# Sheet_1_2021-04-14.net
KiCad netlist of a schematic drawn in Altium Designer
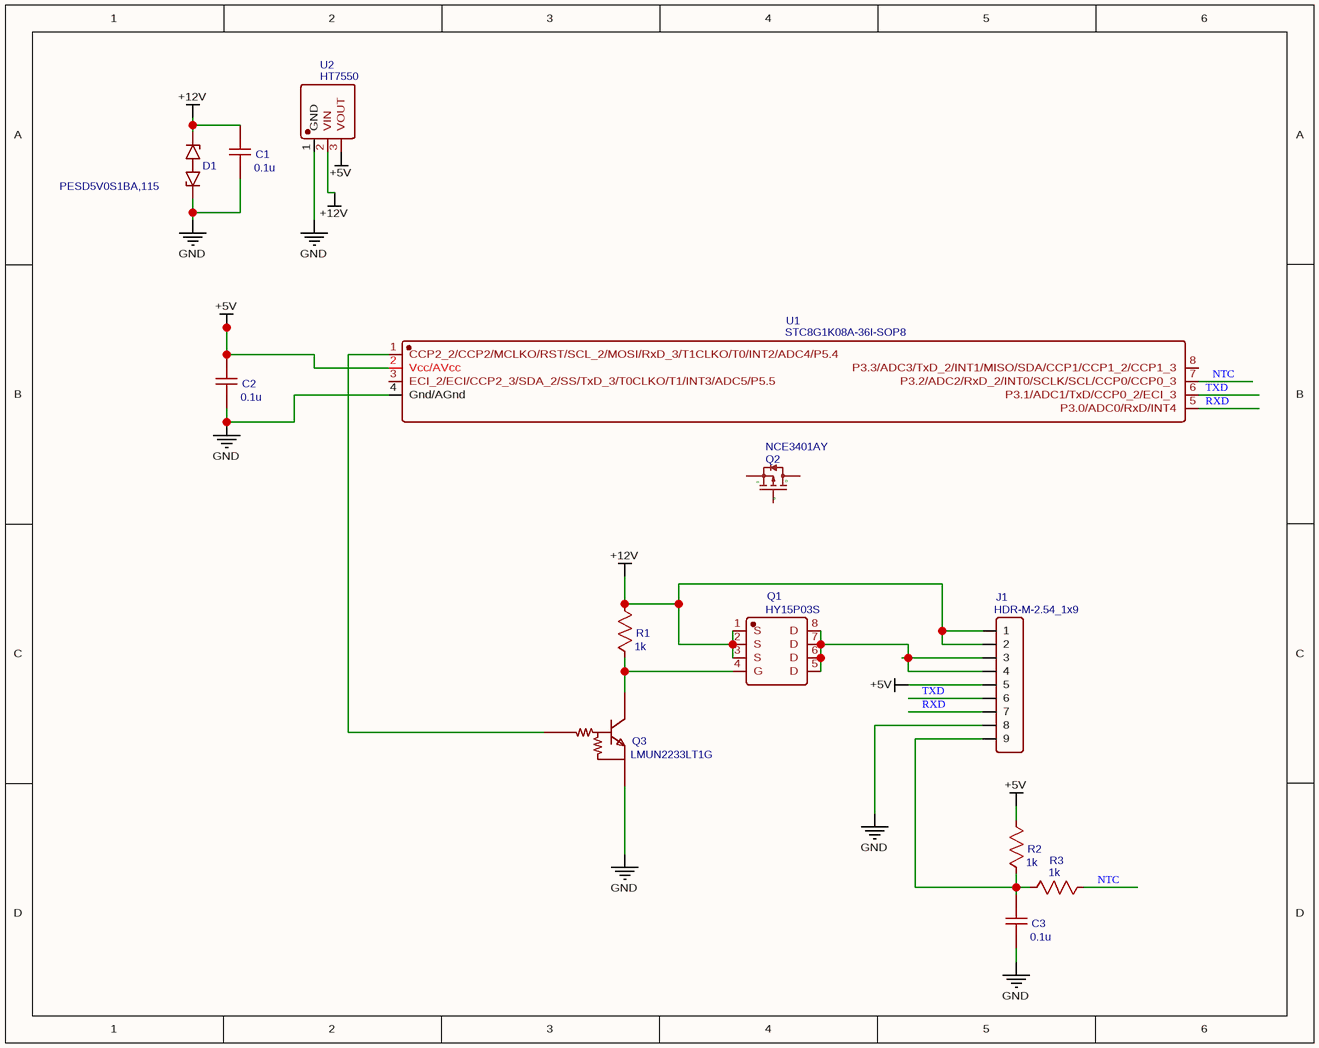
[diagram p0: Sheet_1_2021-04-14.schdoc]

(export (version "E")
  (design (tool "Eeschema 10.0.6"))
  (components
    (comp (ref "C1")
      (value "0.1u")
      (fields (field (name "CONTRIBUTOR") "LCEDA_Lib"))
      (libsource (lib "altium-import") (part "root_1_0.1u_"))
    )
    (comp (ref "C2")
      (value "0.1u")
      (fields (field (name "CONTRIBUTOR") "LCEDA_Lib"))
      (libsource (lib "altium-import") (part "root_1_0.1u_"))
    )
    (comp (ref "C3")
      (value "0.1u")
      (fields (field (name "CONTRIBUTOR") "LCEDA_Lib"))
      (libsource (lib "altium-import") (part "root_1_0.1u_"))
    )
    (comp (ref "D1")
      (value "PESD5V0S1BA,115")
      (fields (field (name "BOM_SUPPLIER PART") "C19224"))
      (libsource (lib "altium-import") (part "root_1_PESD5V0S1BA,115_"))
    )
    (comp (ref "J1")
      (value "HDR-M-2.54_1x9")
      (fields (field (name "BOM_SUPPLIER PART") "C225484") (field (name "CONTRIBUTOR") "LCEDA_Lib"))
      (libsource (lib "altium-import") (part "root_0_HDR-M-2.54_1x9_"))
    )
    (comp (ref "Q1")
      (value "HY15P03S")
      (fields (field (name "BOM_SUPPLIER PART") "C122494"))
      (libsource (lib "altium-import") (part "root_0_HY15P03S_"))
    )
    (comp (ref "Q2")
      (value "NCE3401AY")
      (fields (field (name "BOM_SUPPLIER PART") "C169815") (field (name "CONTRIBUTOR") "LCSC"))
      (libsource (lib "altium-import") (part "root_3_NCE3401AY_"))
    )
    (comp (ref "Q3")
      (value "LMUN2233LT1G")
      (fields (field (name "BOM_SUPPLIER PART") "C12777"))
      (libsource (lib "altium-import") (part "root_0_LMUN2233LT1G_"))
    )
    (comp (ref "R1")
      (value "1k")
      (fields (field (name "CONTRIBUTOR") "LCEDA_Lib"))
      (libsource (lib "altium-import") (part "root_1_1k_"))
    )
    (comp (ref "R2")
      (value "1k")
      (fields (field (name "CONTRIBUTOR") "LCEDA_Lib"))
      (libsource (lib "altium-import") (part "root_1_1k_"))
    )
    (comp (ref "R3")
      (value "1k")
      (fields (field (name "CONTRIBUTOR") "LCEDA_Lib"))
      (libsource (lib "altium-import") (part "root_2_1k_"))
    )
    (comp (ref "U1")
      (value "STC8G1K08A-36I-SOP8")
      (fields (field (name "BOM_SUPPLIER PART") "C915663") (field (name "CONTRIBUTOR") "LCSC"))
      (libsource (lib "altium-import") (part "root_0_STC8G1K08A-36I-SOP8_"))
    )
    (comp (ref "U2")
      (value "HT7550")
      (fields (field (name "BOM_SUPPLIER PART") "C499635") (field (name "CONTRIBUTOR") "LCSC"))
      (libsource (lib "altium-import") (part "root_1_HT7550_"))
    )
  )
  (nets
    (net (code "1") (name "+5V") (class "Default")
      (node (ref "C2") (pin "2") (pinfunction "2_2") (pintype "passive"))
      (node (ref "J1") (pin "5") (pinfunction "5_5") (pintype "passive"))
      (node (ref "R2") (pin "2") (pinfunction "2_2") (pintype "passive"))
      (node (ref "U1") (pin "2") (pinfunction "Vcc/AVcc_2") (pintype "passive"))
      (node (ref "U2") (pin "3") (pinfunction "VOUT_3") (pintype "passive"))
    )
    (net (code "2") (name "+12V") (class "Default")
      (node (ref "C1") (pin "2") (pinfunction "2_2") (pintype "passive"))
      (node (ref "D1") (pin "2") (pinfunction "2_2") (pintype "passive"))
      (node (ref "J1") (pin "1") (pinfunction "1_1") (pintype "passive"))
      (node (ref "J1") (pin "2") (pinfunction "2_2") (pintype "passive"))
      (node (ref "Q1") (pin "1") (pinfunction "S_1") (pintype "passive"))
      (node (ref "Q1") (pin "2") (pinfunction "S_2") (pintype "passive"))
      (node (ref "Q1") (pin "3") (pinfunction "S_3") (pintype "passive"))
      (node (ref "R1") (pin "2") (pinfunction "2_2") (pintype "passive"))
      (node (ref "U2") (pin "2") (pinfunction "VIN_2") (pintype "passive"))
    )
    (net (code "3") (name "/NTC") (class "Default")
      (node (ref "R3") (pin "1") (pinfunction "1_1") (pintype "passive"))
      (node (ref "U1") (pin "7") (pinfunction "P3.2/ADC2/RxD_2/INT0/SCLK/SCL/CCP0/CCP0_3_7") (pintype "passive"))
    )
    (net (code "4") (name "/RXD") (class "Default")
      (node (ref "J1") (pin "7") (pinfunction "7_7") (pintype "passive"))
      (node (ref "U1") (pin "5") (pinfunction "P3.0/ADC0/RxD/INT4_5") (pintype "passive"))
    )
    (net (code "5") (name "/TXD") (class "Default")
      (node (ref "J1") (pin "6") (pinfunction "6_6") (pintype "passive"))
      (node (ref "U1") (pin "6") (pinfunction "P3.1/ADC1/TxD/CCP0_2/ECI_3_6") (pintype "passive"))
    )
    (net (code "6") (name "GND") (class "Default")
      (node (ref "C1") (pin "1") (pinfunction "1_1") (pintype "passive"))
      (node (ref "C2") (pin "1") (pinfunction "1_1") (pintype "passive"))
      (node (ref "C3") (pin "1") (pinfunction "1_1") (pintype "passive"))
      (node (ref "D1") (pin "1") (pinfunction "1_1") (pintype "passive"))
      (node (ref "J1") (pin "8") (pinfunction "8_8") (pintype "passive"))
      (node (ref "Q3") (pin "2") (pinfunction "E_2") (pintype "passive"))
      (node (ref "U1") (pin "4") (pinfunction "Gnd/AGnd_4") (pintype "passive"))
      (node (ref "U2") (pin "1") (pinfunction "GND_1") (pintype "passive"))
    )
    (net (code "7") (name "Net-(C3-Pad2)") (class "Default")
      (node (ref "C3") (pin "2") (pinfunction "2_2") (pintype "passive"))
      (node (ref "J1") (pin "9") (pinfunction "9_9") (pintype "passive"))
      (node (ref "R2") (pin "1") (pinfunction "1_1") (pintype "passive"))
      (node (ref "R3") (pin "2") (pinfunction "2_2") (pintype "passive"))
    )
    (net (code "8") (name "Net-(J1-Pad3)") (class "Default")
      (node (ref "J1") (pin "3") (pinfunction "3_3") (pintype "passive"))
      (node (ref "J1") (pin "4") (pinfunction "4_4") (pintype "passive"))
      (node (ref "Q1") (pin "5") (pinfunction "D_5") (pintype "passive"))
      (node (ref "Q1") (pin "6") (pinfunction "D_6") (pintype "passive"))
      (node (ref "Q1") (pin "7") (pinfunction "D_7") (pintype "passive"))
      (node (ref "Q1") (pin "8") (pinfunction "D_8") (pintype "passive"))
    )
    (net (code "9") (name "Net-(Q1-G)") (class "Default")
      (node (ref "Q1") (pin "4") (pinfunction "G_4") (pintype "passive"))
      (node (ref "Q3") (pin "3") (pinfunction "C_3") (pintype "passive"))
      (node (ref "R1") (pin "1") (pinfunction "1_1") (pintype "passive"))
    )
    (net (code "10") (name "Net-(Q3-B)") (class "Default")
      (node (ref "Q3") (pin "1") (pinfunction "B_1") (pintype "passive"))
      (node (ref "U1") (pin "1") (pinfunction "CCP2_2/CCP2/MCLKO/RST/SCL_2/MOSI/RxD_3/T1CLKO/T0/INT2/ADC4/P5.4_1") (pintype "passive"))
    )
    (net (code "11") (name "unconnected-(Q2-D-Pad3)") (class "Default")
      (node (ref "Q2") (pin "3") (pinfunction "D_3") (pintype "passive"))
    )
    (net (code "12") (name "unconnected-(Q2-G-Pad1)") (class "Default")
      (node (ref "Q2") (pin "1") (pinfunction "G_1") (pintype "passive"))
    )
    (net (code "13") (name "unconnected-(Q2-S-Pad2)") (class "Default")
      (node (ref "Q2") (pin "2") (pinfunction "S_2") (pintype "passive"))
    )
    (net (code "14") (name "unconnected-(U1-ECI_2{slash}ECI{slash}CCP2_3{slash}SDA_2{slash}SS{slash}TxD_3{slash}T0CLKO{slash}T1{slash}INT3{slash}ADC5{slash}P5.5-Pad3)") (class "Default")
      (node (ref "U1") (pin "3") (pinfunction "ECI_2/ECI/CCP2_3/SDA_2/SS/TxD_3/T0CLKO/T1/INT3/ADC5/P5.5_3") (pintype "passive"))
    )
    (net (code "15") (name "unconnected-(U1-P3.3{slash}ADC3{slash}TxD_2{slash}INT1{slash}MISO{slash}SDA{slash}CCP1{slash}CCP1_2{slash}CCP1_3-Pad8)") (class "Default")
      (node (ref "U1") (pin "8") (pinfunction "P3.3/ADC3/TxD_2/INT1/MISO/SDA/CCP1/CCP1_2/CCP1_3_8") (pintype "passive"))
    )
  )
)
